# ext_supply.net
KiCad netlist of a schematic drawn in Altium Designer
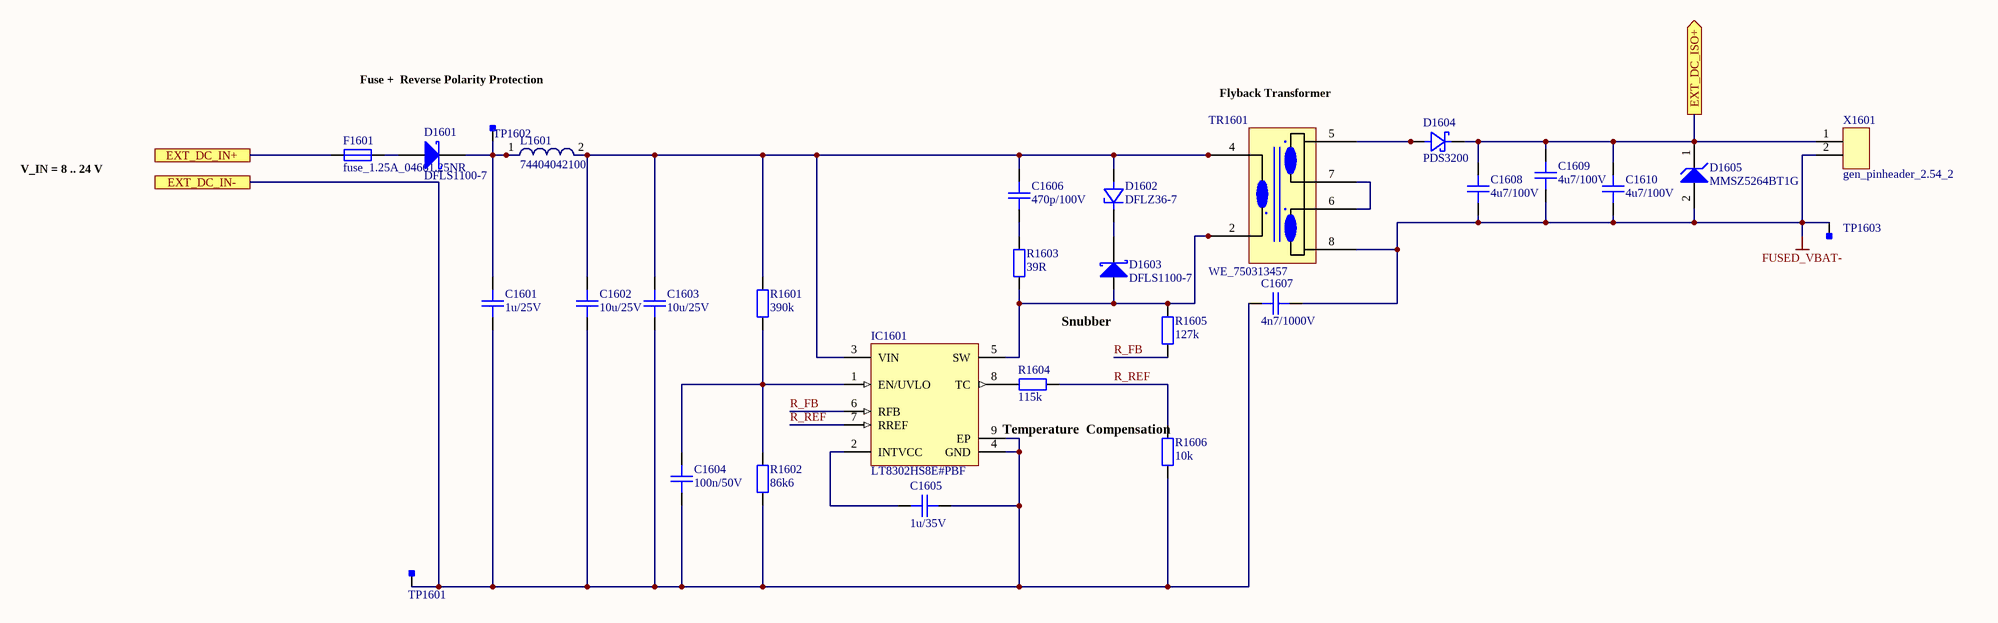
[diagram p0: ext_supply.SchDoc]

(export (version "E")
  (design (tool "Eeschema 10.0.6"))
  (components
    (comp (ref "C1601")
      (value "1u/25V")
      (footprint "CAPC2012X14N")
      (description "MLCC")
      (fields (field (name "PART NUMBER") "gen_C_ceramic_1u_25V_X7R_0805"))
      (libsource (lib "OE750") (part "C"))
    )
    (comp (ref "C1602")
      (value "10u/25V")
      (footprint "CAPC3225X25N")
      (description "MLCC")
      (fields (field (name "PART NUMBER") "gen_C_ceramic_10u_25V_X7R_1210"))
      (libsource (lib "OE750") (part "C"))
    )
    (comp (ref "C1603")
      (value "10u/25V")
      (footprint "CAPC3225X25N")
      (description "MLCC")
      (fields (field (name "PART NUMBER") "gen_C_ceramic_10u_25V_X7R_1210"))
      (libsource (lib "OE750") (part "C"))
    )
    (comp (ref "C1604")
      (value "100n/50V")
      (footprint "CAPC1608X08N")
      (description "MLCC")
      (fields (field (name "PART NUMBER") "gen_C_ceramic_100n_50V_X7R_0603"))
      (libsource (lib "OE750") (part "C"))
    )
    (comp (ref "C1605")
      (value "1u/35V")
      (footprint "CAPC1608X08N")
      (description "MLCC")
      (fields (field (name "PART NUMBER") "gen_C_ceramic_1u_35V_X7R_0603"))
      (libsource (lib "OE750") (part "C"))
    )
    (comp (ref "C1606")
      (value "470p/100V")
      (footprint "CAPC2012X14N")
      (description "MLCC")
      (fields (field (name "PART NUMBER") "gen_C_ceramic_470p_100V_X7R_0805"))
      (libsource (lib "OE750") (part "C"))
    )
    (comp (ref "C1607")
      (value "4n7/1000V")
      (footprint "CAPC4532X16N")
      (description "MLCC")
      (fields (field (name "PART NUMBER") "gen_C_ceramic_4n7_1000V_X7R_1812"))
      (libsource (lib "OE750") (part "C"))
    )
    (comp (ref "C1608")
      (value "4u7/100V")
      (footprint "CAPC3216X18N")
      (description "MLCC")
      (fields (field (name "PART NUMBER") "gen_C_ceramic_4u7_100V_X7S_1206"))
      (libsource (lib "OE750") (part "C"))
    )
    (comp (ref "C1609")
      (value "4u7/100V")
      (footprint "CAPC3216X18N")
      (description "MLCC")
      (fields (field (name "PART NUMBER") "gen_C_ceramic_4u7_100V_X7S_1206"))
      (libsource (lib "OE750") (part "C"))
    )
    (comp (ref "C1610")
      (value "4u7/100V")
      (footprint "CAPC3216X18N")
      (description "MLCC")
      (fields (field (name "PART NUMBER") "gen_C_ceramic_4u7_100V_X7S_1206"))
      (libsource (lib "OE750") (part "C"))
    )
    (comp (ref "D1601")
      (value "DFLS1100-7")
      (footprint "DIOD-POWERDI123-2_V")
      (fields (field (name "MANUFACTURER") "Diodes Inc"))
      (libsource (lib "Altium Content Vault") (part "DSKY-AK-2"))
    )
    (comp (ref "D1602")
      (value "DFLZ36-7")
      (footprint "PowerDI123")
      (description "Zener Diode 36V")
      (fields (field (name "MANUFACTURER") "DIODES Inc"))
      (libsource (lib "OE750") (part "D_Zener"))
    )
    (comp (ref "D1603")
      (value "DFLS1100-7")
      (footprint "DIOD-POWERDI123-2_V")
      (fields (field (name "MANUFACTURER") "Diodes Inc"))
      (libsource (lib "Altium Content Vault") (part "DSKY-AK-2"))
    )
    (comp (ref "D1604")
      (value "PDS3200")
      (footprint "PowerDI5")
      (description "Schottky Diode 3A 200V 780mV")
      (fields (field (name "PART NUMBER") "PDS3200-13") (field (name "MANUFACTURER") "DIODES Inc"))
      (libsource (lib "OE750") (part "PDS3200"))
    )
    (comp (ref "D1605")
      (value "MMSZ5264BT1G")
      (footprint "ONSC-SOD-123-2-425-04_V")
      (description "Zener Voltage Regulator, 500 mW, 2-Pin SOD-123, Pb-Free, Tape and Reel")
      (fields (field (name "MANUFACTURER") "On Semiconductor"))
      (libsource (lib "Altium Content Vault") (part "ONSC-K1A2-2"))
    )
    (comp (ref "F1601")
      (value "fuse_1.25A_04661.25NR")
      (footprint "LITTLEFUSE_466")
      (description "Fuse, Surface Mount, 466 Series, 1.25 A, 63 VAC, 63 VDC, Very Fast Acting, 1206")
      (fields (field (name "MANUFACTURER") "Littlefuse"))
      (libsource (lib "OE750") (part "R_Fuse"))
    )
    (comp (ref "IC1601")
      (value "LT8302HS8E#PBF")
      (footprint "LT-S8E-8_V")
      (fields (field (name "PARTNUMBER") "LT8302"))
      (libsource (lib "Altium Content Vault") (part "LT-LT8302-S8E-8"))
    )
    (comp (ref "L1601")
      (value "74404042100")
      (footprint "WE-LQS 4018")
      (description "WE-LQS SMD Power Inductor, L=10 µH")
      (fields (field (name "MANUFACTURER") "Wuerth Elektronik"))
      (libsource (lib "Altium Content Vault") (part "WE-IND-INDUCTOR-2"))
    )
    (comp (ref "R1601")
      (value "390k")
      (footprint "RESC1608X05N")
      (description "SMD Resistor 390k 0603")
      (fields (field (name "PART NUMBER") "gen_R_390k_0603") (field (name "TOLERANCE") "1%"))
      (libsource (lib "OE750") (part "R"))
    )
    (comp (ref "R1602")
      (value "86k6")
      (footprint "RESC1608X05N")
      (description "SMD Resistor 86k6 0603")
      (fields (field (name "PART NUMBER") "gen_R_86k6_0603") (field (name "TOLERANCE") "1%"))
      (libsource (lib "OE750") (part "R"))
    )
    (comp (ref "R1603")
      (value "39R")
      (footprint "RESC2012X05N")
      (description "SMD Resistor 39R 0805")
      (fields (field (name "PART NUMBER") "gen_R_39R_0805") (field (name "TOLERANCE") "1%"))
      (libsource (lib "OE750") (part "R"))
    )
    (comp (ref "R1604")
      (value "115k")
      (footprint "RESC1608X05N")
      (description "SMD Resistor 115k 0603")
      (fields (field (name "PART NUMBER") "gen_R_115k_0603") (field (name "TOLERANCE") "1%"))
      (libsource (lib "OE750") (part "R"))
    )
    (comp (ref "R1605")
      (value "127k")
      (footprint "RESC1608X05N")
      (description "SMD Resistor 127k 0603")
      (fields (field (name "PART NUMBER") "gen_R_127k_0603") (field (name "TOLERANCE") "1%"))
      (libsource (lib "OE750") (part "R"))
    )
    (comp (ref "R1606")
      (value "10k")
      (footprint "RESC1608X05N")
      (description "SMD Resistor 10k 0603")
      (fields (field (name "PART NUMBER") "gen_R_10k_0603") (field (name "TOLERANCE") "1%"))
      (libsource (lib "OE750") (part "R"))
    )
    (comp (ref "TP1601")
      (value "Testpoint_Square")
      (footprint "Testpoint_S1")
      (description "Testpoint, square")
      (libsource (lib "OE750") (part "Testpoint_Square"))
    )
    (comp (ref "TP1602")
      (value "Testpoint_Square")
      (footprint "Testpoint_S1")
      (description "Testpoint, square")
      (libsource (lib "OE750") (part "Testpoint_Square"))
    )
    (comp (ref "TP1603")
      (value "Testpoint_Square")
      (footprint "Testpoint_S1")
      (description "Testpoint, square")
      (libsource (lib "OE750") (part "Testpoint_Square"))
    )
    (comp (ref "TR1601")
      (value "WE_750313457")
      (footprint "WE_750313457")
      (description "MID-FLYLT Flyback Transformers for Linear Technology")
      (fields (field (name "MANUFACTURER") "Würth Elektronik"))
      (libsource (lib "OE750") (part "WE_750313457"))
    )
    (comp (ref "X1601")
      (value "gen_pinheader_2.54_2")
      (footprint "Pinheader_2.54_2")
      (description "Standard Pinheader, THD, gerade, 2.54mm")
      (libsource (lib "OE750") (part "X2"))
    )
  )
  (nets
    (net (code "1") (name "/EXT_DC_IN+") (class "Default")
      (node (ref "F1601") (pin "1") (pinfunction "1_1") (pintype "passive"))
    )
    (net (code "2") (name "/EXT_DC_IN-") (class "Default")
      (node (ref "C1601") (pin "1") (pinfunction "1_1") (pintype "passive"))
      (node (ref "C1602") (pin "1") (pinfunction "1_1") (pintype "passive"))
      (node (ref "C1603") (pin "1") (pinfunction "1_1") (pintype "passive"))
      (node (ref "C1604") (pin "1") (pinfunction "1_1") (pintype "passive"))
      (node (ref "C1605") (pin "1") (pinfunction "1_1") (pintype "passive"))
      (node (ref "C1607") (pin "1") (pinfunction "1_1") (pintype "passive"))
      (node (ref "IC1601") (pin "4") (pinfunction "GND_4") (pintype "power_in"))
      (node (ref "IC1601") (pin "9") (pinfunction "EP_9") (pintype "power_in"))
      (node (ref "R1602") (pin "1") (pinfunction "1_1") (pintype "passive"))
      (node (ref "R1606") (pin "1") (pinfunction "1_1") (pintype "passive"))
      (node (ref "TP1601") (pin "1") (pinfunction "1_1") (pintype "passive"))
    )
    (net (code "3") (name "/EXT_DC_ISO+") (class "Default")
      (node (ref "C1608") (pin "2") (pinfunction "2_2") (pintype "passive"))
      (node (ref "C1609") (pin "2") (pinfunction "2_2") (pintype "passive"))
      (node (ref "C1610") (pin "2") (pinfunction "2_2") (pintype "passive"))
      (node (ref "D1604") (pin "1") (pinfunction "C_1") (pintype "passive"))
      (node (ref "D1605") (pin "1") (pinfunction "K_1") (pintype "passive"))
      (node (ref "X1601") (pin "1") (pintype "passive"))
    )
    (net (code "4") (name "/R_FB") (class "Default")
      (node (ref "IC1601") (pin "6") (pinfunction "RFB_6") (pintype "input"))
      (node (ref "R1605") (pin "1") (pinfunction "1_1") (pintype "passive"))
    )
    (net (code "5") (name "/R_REF") (class "Default")
      (node (ref "IC1601") (pin "7") (pinfunction "RREF_7") (pintype "input"))
      (node (ref "R1604") (pin "2") (pinfunction "2_2") (pintype "passive"))
      (node (ref "R1606") (pin "2") (pinfunction "2_2") (pintype "passive"))
    )
    (net (code "6") (name "FUSED_VBAT-") (class "Default")
      (node (ref "C1607") (pin "2") (pinfunction "2_2") (pintype "passive"))
      (node (ref "C1608") (pin "1") (pinfunction "1_1") (pintype "passive"))
      (node (ref "C1609") (pin "1") (pinfunction "1_1") (pintype "passive"))
      (node (ref "C1610") (pin "1") (pinfunction "1_1") (pintype "passive"))
      (node (ref "D1605") (pin "2") (pinfunction "A_2") (pintype "passive"))
      (node (ref "TP1603") (pin "1") (pinfunction "1_1") (pintype "passive"))
      (node (ref "TR1601") (pin "8") (pinfunction "8_8") (pintype "passive"))
      (node (ref "X1601") (pin "2") (pintype "passive"))
    )
    (net (code "7") (name "Net-(C1606-Pad1)") (class "Default")
      (node (ref "C1606") (pin "1") (pinfunction "1_1") (pintype "passive"))
      (node (ref "R1603") (pin "2") (pinfunction "2_2") (pintype "passive"))
    )
    (net (code "8") (name "Net-(D1601-A)") (class "Default")
      (node (ref "D1601") (pin "1") (pinfunction "A_1") (pintype "passive"))
      (node (ref "F1601") (pin "2") (pinfunction "2_2") (pintype "passive"))
    )
    (net (code "9") (name "Net-(D1601-K)") (class "Default")
      (node (ref "C1601") (pin "2") (pinfunction "2_2") (pintype "passive"))
      (node (ref "D1601") (pin "2") (pinfunction "K_2") (pintype "passive"))
      (node (ref "L1601") (pin "1") (pinfunction "1_1") (pintype "passive"))
      (node (ref "TP1602") (pin "1") (pinfunction "1_1") (pintype "passive"))
    )
    (net (code "10") (name "Net-(D1602-A)") (class "Default")
      (node (ref "C1602") (pin "2") (pinfunction "2_2") (pintype "passive"))
      (node (ref "C1603") (pin "2") (pinfunction "2_2") (pintype "passive"))
      (node (ref "C1606") (pin "2") (pinfunction "2_2") (pintype "passive"))
      (node (ref "D1602") (pin "2") (pinfunction "A_2") (pintype "passive"))
      (node (ref "IC1601") (pin "3") (pinfunction "VIN_3") (pintype "power_in"))
      (node (ref "L1601") (pin "2") (pinfunction "2_2") (pintype "passive"))
      (node (ref "R1601") (pin "2") (pinfunction "2_2") (pintype "passive"))
      (node (ref "TR1601") (pin "3") (pinfunction "3_3") (pintype "passive"))
      (node (ref "TR1601") (pin "4") (pinfunction "4_4") (pintype "passive"))
    )
    (net (code "11") (name "Net-(D1602-K)") (class "Default")
      (node (ref "D1602") (pin "1") (pinfunction "K_1") (pintype "passive"))
      (node (ref "D1603") (pin "2") (pinfunction "K_2") (pintype "passive"))
    )
    (net (code "12") (name "Net-(D1603-A)") (class "Default")
      (node (ref "D1603") (pin "1") (pinfunction "A_1") (pintype "passive"))
      (node (ref "IC1601") (pin "5") (pinfunction "SW_5") (pintype "power_in"))
      (node (ref "R1603") (pin "1") (pinfunction "1_1") (pintype "passive"))
      (node (ref "R1605") (pin "2") (pinfunction "2_2") (pintype "passive"))
      (node (ref "TR1601") (pin "1") (pinfunction "1_1") (pintype "passive"))
      (node (ref "TR1601") (pin "2") (pinfunction "2_2") (pintype "passive"))
    )
    (net (code "13") (name "Net-(D1604-A-Pad2)") (class "Default")
      (node (ref "D1604") (pin "2") (pinfunction "A_2") (pintype "passive"))
      (node (ref "D1604") (pin "3") (pinfunction "A_3") (pintype "passive"))
      (node (ref "TR1601") (pin "5") (pinfunction "5_5") (pintype "passive"))
    )
    (net (code "14") (name "Net-(IC1601-EN{slash}UVLO)") (class "Default")
      (node (ref "C1604") (pin "2") (pinfunction "2_2") (pintype "passive"))
      (node (ref "IC1601") (pin "1") (pinfunction "EN/UVLO_1") (pintype "input"))
      (node (ref "R1601") (pin "1") (pinfunction "1_1") (pintype "passive"))
      (node (ref "R1602") (pin "2") (pinfunction "2_2") (pintype "passive"))
    )
    (net (code "15") (name "Net-(IC1601-INTVCC)") (class "Default")
      (node (ref "C1605") (pin "2") (pinfunction "2_2") (pintype "passive"))
      (node (ref "IC1601") (pin "2") (pinfunction "INTVCC_2") (pintype "power_in"))
    )
    (net (code "16") (name "Net-(IC1601-TC)") (class "Default")
      (node (ref "IC1601") (pin "8") (pinfunction "TC_8") (pintype "output"))
      (node (ref "R1604") (pin "1") (pinfunction "1_1") (pintype "passive"))
    )
    (net (code "17") (name "Net-(TR1601-Pad6)") (class "Default")
      (node (ref "TR1601") (pin "6") (pinfunction "6_6") (pintype "passive"))
      (node (ref "TR1601") (pin "7") (pinfunction "7_7") (pintype "passive"))
    )
  )
)
